# Arduino.net
KiCad netlist of a schematic drawn in EAGLE
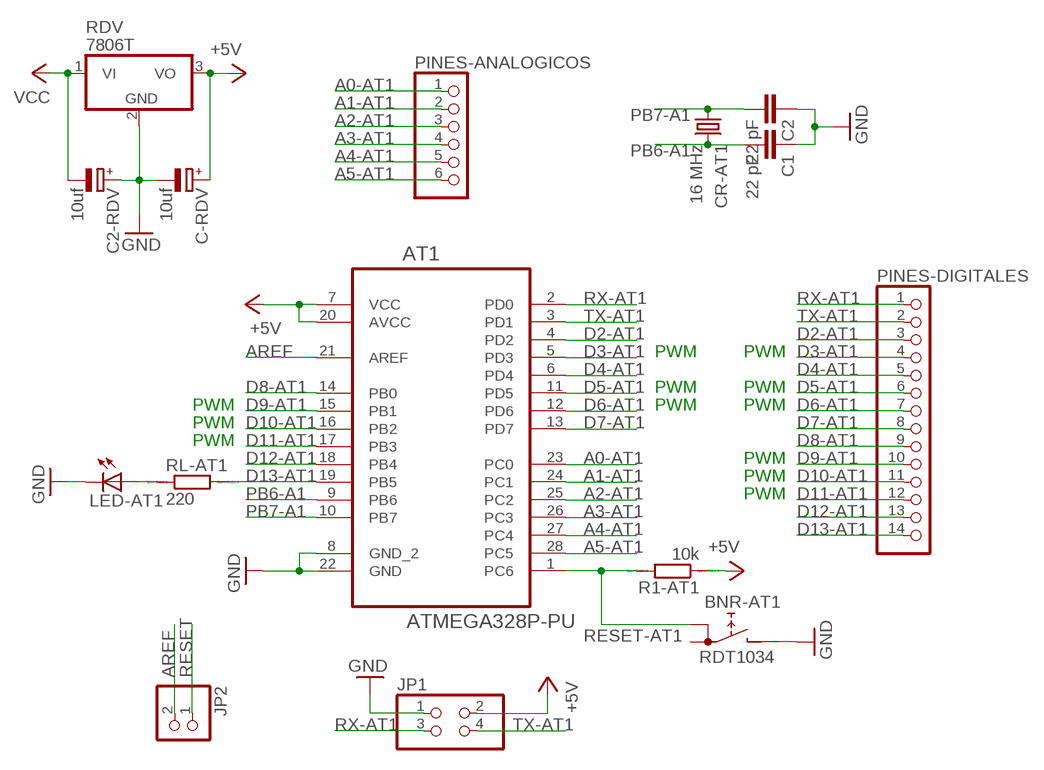
[diagram p0: schematic, sheet 1]

(export (version "E")
  (design (tool "Eeschema 10.0.6"))
  (components
    (comp (ref "AT1")
      (value "ATMEGA328P-PU")
      (footprint "eagle-import:DIP254P762X457-28")
      (libsource (lib "eagle-import") (part "ATMEGA328P-PU"))
    )
    (comp (ref "BNR-AT1")
      (value "RDT1034")
      (footprint "eagle-import:RDT1034")
      (libsource (lib "eagle-import") (part "RDT1034"))
    )
    (comp (ref "C-RDV")
      (value "10uf")
      (footprint "eagle-import:TT5D9")
      (libsource (lib "eagle-import") (part "CPOL-EUTT5D9"))
    )
    (comp (ref "C1")
      (value "22 pF")
      (footprint "eagle-import:C2.5-3")
      (libsource (lib "eagle-import") (part "C2,5-3"))
    )
    (comp (ref "C2")
      (value "22 pF")
      (footprint "eagle-import:C2.5-3")
      (libsource (lib "eagle-import") (part "C2,5-3"))
    )
    (comp (ref "C2-RDV")
      (value "10uf")
      (footprint "eagle-import:TT5D9")
      (libsource (lib "eagle-import") (part "CPOL-EUTT5D9"))
    )
    (comp (ref "CR-AT1")
      (value "16 MHz")
      (footprint "eagle-import:HC49U70")
      (libsource (lib "eagle-import") (part "CRYSTALHC49U70"))
    )
    (comp (ref "JP1")
      (value "PINHD-2X2")
      (footprint "eagle-import:2X02")
      (libsource (lib "eagle-import") (part "PINHD-2X2"))
    )
    (comp (ref "JP2")
      (value "PINHD-1X2")
      (footprint "eagle-import:1X02")
      (libsource (lib "eagle-import") (part "PINHD-1X2"))
    )
    (comp (ref "LED-AT1")
      (value "LED5MM")
      (footprint "eagle-import:LED5MM")
      (libsource (lib "eagle-import") (part "LED5MM"))
    )
    (comp (ref "PINES-ANALOGICOS")
      (value "PINHD-1X6")
      (footprint "eagle-import:1X06")
      (libsource (lib "eagle-import") (part "PINHD-1X6"))
    )
    (comp (ref "PINES-DIGITALES")
      (value "PINHD-1X14")
      (footprint "eagle-import:1X14")
      (libsource (lib "eagle-import") (part "PINHD-1X14"))
    )
    (comp (ref "R1-AT1")
      (value "10k")
      (footprint "eagle-import:0207_7")
      (libsource (lib "eagle-import") (part "R-EU_0207_7"))
    )
    (comp (ref "RDV")
      (value "7806T")
      (footprint "eagle-import:TO220H")
      (libsource (lib "eagle-import") (part "78T06"))
    )
    (comp (ref "RL-AT1")
      (value "220")
      (footprint "eagle-import:0207_7")
      (libsource (lib "eagle-import") (part "R-EU_0207_7"))
    )
  )
  (nets
    (net (code "1") (name "+5V") (class "Default")
      (node (ref "AT1") (pin "20") (pinfunction "AVCC_20") (pintype "power_in"))
      (node (ref "AT1") (pin "7") (pinfunction "VCC_7") (pintype "power_in"))
      (node (ref "C-RDV") (pin "+") (pinfunction "+_+") (pintype "passive"))
      (node (ref "JP1") (pin "2") (pinfunction "2_2") (pintype "passive"))
      (node (ref "R1-AT1") (pin "1") (pinfunction "1_1") (pintype "passive"))
      (node (ref "RDV") (pin "3") (pinfunction "VO_3") (pintype "passive"))
    )
    (net (code "2") (name "/A0-AT1") (class "Default")
      (node (ref "AT1") (pin "23") (pinfunction "PC0_23") (pintype "bidirectional"))
      (node (ref "PINES-ANALOGICOS") (pin "1") (pinfunction "1_1") (pintype "passive"))
    )
    (net (code "3") (name "/A1-AT1") (class "Default")
      (node (ref "AT1") (pin "24") (pinfunction "PC1_24") (pintype "bidirectional"))
      (node (ref "PINES-ANALOGICOS") (pin "2") (pinfunction "2_2") (pintype "passive"))
    )
    (net (code "4") (name "/A2-AT1") (class "Default")
      (node (ref "AT1") (pin "25") (pinfunction "PC2_25") (pintype "bidirectional"))
      (node (ref "PINES-ANALOGICOS") (pin "3") (pinfunction "3_3") (pintype "passive"))
    )
    (net (code "5") (name "/A3-AT1") (class "Default")
      (node (ref "AT1") (pin "26") (pinfunction "PC3_26") (pintype "bidirectional"))
      (node (ref "PINES-ANALOGICOS") (pin "4") (pinfunction "4_4") (pintype "passive"))
    )
    (net (code "6") (name "/A4-AT1") (class "Default")
      (node (ref "AT1") (pin "27") (pinfunction "PC4_27") (pintype "bidirectional"))
      (node (ref "PINES-ANALOGICOS") (pin "5") (pinfunction "5_5") (pintype "passive"))
    )
    (net (code "7") (name "/A5-AT1") (class "Default")
      (node (ref "AT1") (pin "28") (pinfunction "PC5_28") (pintype "bidirectional"))
      (node (ref "PINES-ANALOGICOS") (pin "6") (pinfunction "6_6") (pintype "passive"))
    )
    (net (code "8") (name "/AREF") (class "Default")
      (node (ref "AT1") (pin "21") (pinfunction "AREF_21") (pintype "input"))
      (node (ref "JP2") (pin "2") (pinfunction "2_2") (pintype "passive"))
    )
    (net (code "9") (name "/D2-AT1") (class "Default")
      (node (ref "AT1") (pin "4") (pinfunction "PD2_4") (pintype "bidirectional"))
      (node (ref "PINES-DIGITALES") (pin "3") (pinfunction "3_3") (pintype "passive"))
    )
    (net (code "10") (name "/D3-AT1") (class "Default")
      (node (ref "AT1") (pin "5") (pinfunction "PD3_5") (pintype "bidirectional"))
      (node (ref "PINES-DIGITALES") (pin "4") (pinfunction "4_4") (pintype "passive"))
    )
    (net (code "11") (name "/D4-AT1") (class "Default")
      (node (ref "AT1") (pin "6") (pinfunction "PD4_6") (pintype "bidirectional"))
      (node (ref "PINES-DIGITALES") (pin "5") (pinfunction "5_5") (pintype "passive"))
    )
    (net (code "12") (name "/D5-AT1") (class "Default")
      (node (ref "AT1") (pin "11") (pinfunction "PD5_11") (pintype "bidirectional"))
      (node (ref "PINES-DIGITALES") (pin "6") (pinfunction "6_6") (pintype "passive"))
    )
    (net (code "13") (name "/D6-AT1") (class "Default")
      (node (ref "AT1") (pin "12") (pinfunction "PD6_12") (pintype "bidirectional"))
      (node (ref "PINES-DIGITALES") (pin "7") (pinfunction "7_7") (pintype "passive"))
    )
    (net (code "14") (name "/D7-AT1") (class "Default")
      (node (ref "AT1") (pin "13") (pinfunction "PD7_13") (pintype "bidirectional"))
      (node (ref "PINES-DIGITALES") (pin "8") (pinfunction "8_8") (pintype "passive"))
    )
    (net (code "15") (name "/D8-AT1") (class "Default")
      (node (ref "AT1") (pin "14") (pinfunction "PB0_14") (pintype "bidirectional"))
      (node (ref "PINES-DIGITALES") (pin "9") (pinfunction "9_9") (pintype "passive"))
    )
    (net (code "16") (name "/D9-AT1") (class "Default")
      (node (ref "AT1") (pin "15") (pinfunction "PB1_15") (pintype "bidirectional"))
      (node (ref "PINES-DIGITALES") (pin "10") (pinfunction "10_10") (pintype "passive"))
    )
    (net (code "17") (name "/D10-AT1") (class "Default")
      (node (ref "AT1") (pin "16") (pinfunction "PB2_16") (pintype "bidirectional"))
      (node (ref "PINES-DIGITALES") (pin "11") (pinfunction "11_11") (pintype "passive"))
    )
    (net (code "18") (name "/D11-AT1") (class "Default")
      (node (ref "AT1") (pin "17") (pinfunction "PB3_17") (pintype "bidirectional"))
      (node (ref "PINES-DIGITALES") (pin "12") (pinfunction "12_12") (pintype "passive"))
    )
    (net (code "19") (name "/D12-AT1") (class "Default")
      (node (ref "AT1") (pin "18") (pinfunction "PB4_18") (pintype "bidirectional"))
      (node (ref "PINES-DIGITALES") (pin "13") (pinfunction "13_13") (pintype "passive"))
    )
    (net (code "20") (name "/D13-AT1") (class "Default")
      (node (ref "AT1") (pin "19") (pinfunction "PB5_19") (pintype "bidirectional"))
      (node (ref "PINES-DIGITALES") (pin "14") (pinfunction "14_14") (pintype "passive"))
      (node (ref "RL-AT1") (pin "2") (pinfunction "2_2") (pintype "passive"))
    )
    (net (code "21") (name "/PB6-A1") (class "Default")
      (node (ref "AT1") (pin "9") (pinfunction "PB6_9") (pintype "bidirectional"))
      (node (ref "C1") (pin "2") (pinfunction "2_2") (pintype "passive"))
      (node (ref "CR-AT1") (pin "2") (pinfunction "2_2") (pintype "passive"))
    )
    (net (code "22") (name "/PB7-A1") (class "Default")
      (node (ref "AT1") (pin "10") (pinfunction "PB7_10") (pintype "bidirectional"))
      (node (ref "C2") (pin "2") (pinfunction "2_2") (pintype "passive"))
      (node (ref "CR-AT1") (pin "1") (pinfunction "1_1") (pintype "passive"))
    )
    (net (code "23") (name "/RESET") (class "Default")
      (node (ref "JP2") (pin "1") (pinfunction "1_1") (pintype "passive"))
    )
    (net (code "24") (name "/RESET-AT1") (class "Default")
      (node (ref "AT1") (pin "1") (pinfunction "PC6_1") (pintype "bidirectional"))
      (node (ref "BNR-AT1") (pin "A") (pinfunction "A_A") (pintype "passive"))
      (node (ref "R1-AT1") (pin "2") (pinfunction "2_2") (pintype "passive"))
    )
    (net (code "25") (name "/RX-AT1") (class "Default")
      (node (ref "AT1") (pin "2") (pinfunction "PD0_2") (pintype "bidirectional"))
      (node (ref "JP1") (pin "3") (pinfunction "3_3") (pintype "passive"))
      (node (ref "PINES-DIGITALES") (pin "1") (pinfunction "1_1") (pintype "passive"))
    )
    (net (code "26") (name "/TX-AT1") (class "Default")
      (node (ref "AT1") (pin "3") (pinfunction "PD1_3") (pintype "bidirectional"))
      (node (ref "JP1") (pin "4") (pinfunction "4_4") (pintype "passive"))
      (node (ref "PINES-DIGITALES") (pin "2") (pinfunction "2_2") (pintype "passive"))
    )
    (net (code "27") (name "GND") (class "Default")
      (node (ref "AT1") (pin "22") (pinfunction "GND_22") (pintype "passive"))
      (node (ref "AT1") (pin "8") (pinfunction "GND_2_8") (pintype "passive"))
      (node (ref "BNR-AT1") (pin "B") (pinfunction "B_B") (pintype "passive"))
      (node (ref "C-RDV") (pin "-") (pinfunction "-_-") (pintype "passive"))
      (node (ref "C1") (pin "1") (pinfunction "1_1") (pintype "passive"))
      (node (ref "C2") (pin "1") (pinfunction "1_1") (pintype "passive"))
      (node (ref "C2-RDV") (pin "+") (pinfunction "+_+") (pintype "passive"))
      (node (ref "JP1") (pin "1") (pinfunction "1_1") (pintype "passive"))
      (node (ref "LED-AT1") (pin "K") (pinfunction "C_K") (pintype "passive"))
      (node (ref "RDV") (pin "2") (pinfunction "GND_2") (pintype "passive"))
    )
    (net (code "28") (name "Net-(LED-AT1-PadA)") (class "Default")
      (node (ref "LED-AT1") (pin "A") (pinfunction "A_A") (pintype "passive"))
      (node (ref "RL-AT1") (pin "1") (pinfunction "1_1") (pintype "passive"))
    )
    (net (code "29") (name "VCC") (class "Default")
      (node (ref "C2-RDV") (pin "-") (pinfunction "-_-") (pintype "passive"))
      (node (ref "RDV") (pin "1") (pinfunction "VI_1") (pintype "input"))
    )
    (net (code "30") (name "unconnected-(BNR-AT1-PadA1)") (class "Default")
      (node (ref "BNR-AT1") (pin "A1") (pinfunction "A1_A1") (pintype "passive"))
    )
  )
)
